# Jetson_Nano_Connector.net
KiCad netlist of a schematic drawn in Altium Designer
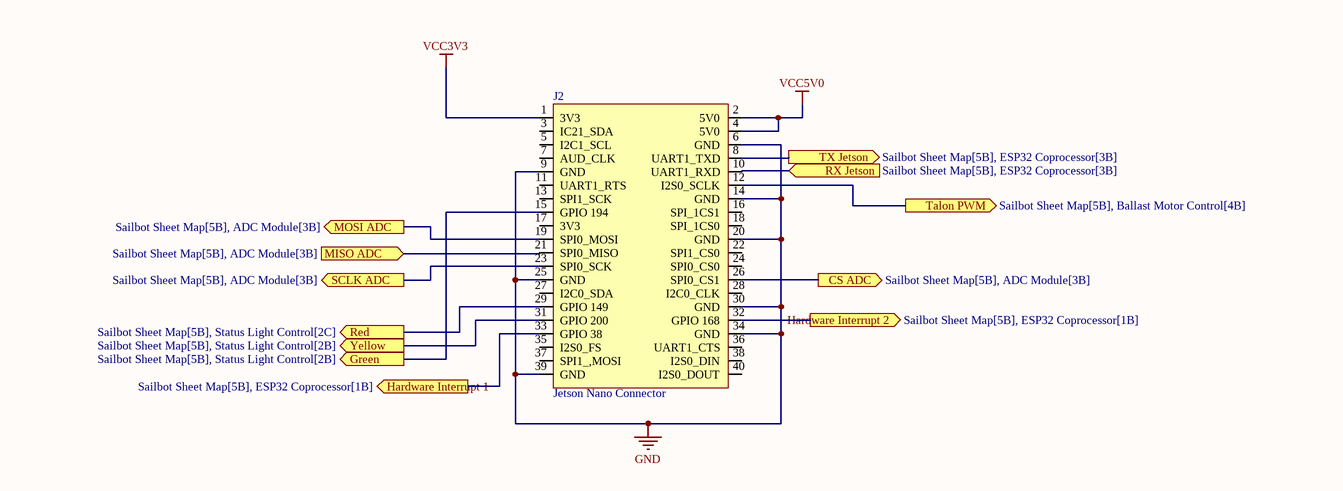
[diagram p0: Jetson Nano Connector.SchDoc]

(export (version "E")
  (design (tool "Eeschema 10.0.6"))
  (components
    (comp (ref "J2")
      (value "Jetson Nano Connector")
      (footprint "Jetson Nano Header")
      (libsource (lib "Sailbot Library") (part "Jetson Nano Connector"))
    )
  )
  (nets
    (net (code "1") (name "/CS ADC") (class "Default")
      (node (ref "J2") (pin "26") (pinfunction "SPI0_CS1_26") (pintype "passive"))
    )
    (net (code "2") (name "/Green") (class "Default")
      (node (ref "J2") (pin "15") (pinfunction "GPIO_194_15") (pintype "passive"))
    )
    (net (code "3") (name "/Hardware Interrupt 1") (class "Default")
      (node (ref "J2") (pin "33") (pinfunction "GPIO_38_33") (pintype "passive"))
    )
    (net (code "4") (name "/Hardware Interrupt 2") (class "Default")
      (node (ref "J2") (pin "32") (pinfunction "GPIO_168_32") (pintype "passive"))
    )
    (net (code "5") (name "/MISO ADC") (class "Default")
      (node (ref "J2") (pin "21") (pinfunction "SPI0_MISO_21") (pintype "passive"))
    )
    (net (code "6") (name "/MOSI ADC") (class "Default")
      (node (ref "J2") (pin "19") (pinfunction "SPI0_MOSI_19") (pintype "passive"))
    )
    (net (code "7") (name "/RX Jetson") (class "Default")
      (node (ref "J2") (pin "10") (pinfunction "UART1_RXD_10") (pintype "passive"))
    )
    (net (code "8") (name "/Red") (class "Default")
      (node (ref "J2") (pin "29") (pinfunction "GPIO_149_29") (pintype "passive"))
    )
    (net (code "9") (name "/SCLK ADC") (class "Default")
      (node (ref "J2") (pin "23") (pinfunction "SPI0_SCK_23") (pintype "passive"))
    )
    (net (code "10") (name "/TX Jetson") (class "Default")
      (node (ref "J2") (pin "8") (pinfunction "UART1_TXD_8") (pintype "passive"))
    )
    (net (code "11") (name "/Talon PWM") (class "Default")
      (node (ref "J2") (pin "12") (pinfunction "I2S0_SCLK_12") (pintype "passive"))
    )
    (net (code "12") (name "/Yellow") (class "Default")
      (node (ref "J2") (pin "31") (pinfunction "GPIO_200_31") (pintype "passive"))
    )
    (net (code "13") (name "GND") (class "Default")
      (node (ref "J2") (pin "14") (pinfunction "GND_14") (pintype "passive"))
      (node (ref "J2") (pin "20") (pinfunction "GND_20") (pintype "passive"))
      (node (ref "J2") (pin "25") (pinfunction "GND_25") (pintype "passive"))
      (node (ref "J2") (pin "30") (pinfunction "GND_30") (pintype "passive"))
      (node (ref "J2") (pin "34") (pinfunction "GND_34") (pintype "passive"))
      (node (ref "J2") (pin "39") (pinfunction "GND_39") (pintype "passive"))
      (node (ref "J2") (pin "6") (pinfunction "GND_6") (pintype "passive"))
      (node (ref "J2") (pin "9") (pinfunction "GND_9") (pintype "passive"))
    )
    (net (code "14") (name "VCC3V3") (class "Default")
      (node (ref "J2") (pin "1") (pinfunction "3V3_1") (pintype "passive"))
    )
    (net (code "15") (name "VCC5V0") (class "Default")
      (node (ref "J2") (pin "2") (pinfunction "5V0_2") (pintype "passive"))
      (node (ref "J2") (pin "4") (pinfunction "5V0_4") (pintype "passive"))
    )
    (net (code "16") (name "unconnected-(J2-3V3-Pad17)") (class "Default")
      (node (ref "J2") (pin "17") (pinfunction "3V3_17") (pintype "passive"))
    )
    (net (code "17") (name "unconnected-(J2-AUD_CLK-Pad7)") (class "Default")
      (node (ref "J2") (pin "7") (pinfunction "AUD_CLK_7") (pintype "passive"))
    )
    (net (code "18") (name "unconnected-(J2-I2C0_CLK-Pad28)") (class "Default")
      (node (ref "J2") (pin "28") (pinfunction "I2C0_CLK_28") (pintype "passive"))
    )
    (net (code "19") (name "unconnected-(J2-I2C0_SDA-Pad27)") (class "Default")
      (node (ref "J2") (pin "27") (pinfunction "I2C0_SDA_27") (pintype "passive"))
    )
    (net (code "20") (name "unconnected-(J2-I2C1_SCL-Pad5)") (class "Default")
      (node (ref "J2") (pin "5") (pinfunction "I2C1_SCL_5") (pintype "passive"))
    )
    (net (code "21") (name "unconnected-(J2-I2S0_DIN-Pad38)") (class "Default")
      (node (ref "J2") (pin "38") (pinfunction "I2S0_DIN_38") (pintype "passive"))
    )
    (net (code "22") (name "unconnected-(J2-I2S0_DOUT-Pad40)") (class "Default")
      (node (ref "J2") (pin "40") (pinfunction "I2S0_DOUT_40") (pintype "passive"))
    )
    (net (code "23") (name "unconnected-(J2-I2S0_FS-Pad35)") (class "Default")
      (node (ref "J2") (pin "35") (pinfunction "I2S0_FS_35") (pintype "passive"))
    )
    (net (code "24") (name "unconnected-(J2-IC21_SDA-Pad3)") (class "Default")
      (node (ref "J2") (pin "3") (pinfunction "IC21_SDA_3") (pintype "passive"))
    )
    (net (code "25") (name "unconnected-(J2-SPI0_CS0-Pad24)") (class "Default")
      (node (ref "J2") (pin "24") (pinfunction "SPI0_CS0_24") (pintype "passive"))
    )
    (net (code "26") (name "unconnected-(J2-SPI1_,MOSI-Pad37)") (class "Default")
      (node (ref "J2") (pin "37") (pinfunction "SPI1_,MOSI_37") (pintype "passive"))
    )
    (net (code "27") (name "unconnected-(J2-SPI1_CS0-Pad22)") (class "Default")
      (node (ref "J2") (pin "22") (pinfunction "SPI1_CS0_22") (pintype "passive"))
    )
    (net (code "28") (name "unconnected-(J2-SPI1_SCK-Pad13)") (class "Default")
      (node (ref "J2") (pin "13") (pinfunction "SPI1_SCK_13") (pintype "passive"))
    )
    (net (code "29") (name "unconnected-(J2-SPI_1CS0-Pad18)") (class "Default")
      (node (ref "J2") (pin "18") (pinfunction "SPI_1CS0_18") (pintype "passive"))
    )
    (net (code "30") (name "unconnected-(J2-SPI_1CS1-Pad16)") (class "Default")
      (node (ref "J2") (pin "16") (pinfunction "SPI_1CS1_16") (pintype "passive"))
    )
    (net (code "31") (name "unconnected-(J2-UART1_CTS-Pad36)") (class "Default")
      (node (ref "J2") (pin "36") (pinfunction "UART1_CTS_36") (pintype "passive"))
    )
    (net (code "32") (name "unconnected-(J2-UART1_RTS-Pad11)") (class "Default")
      (node (ref "J2") (pin "11") (pinfunction "UART1_RTS_11") (pintype "passive"))
    )
  )
)
